# GPS.net
KiCad netlist of a schematic drawn in Altium Designer
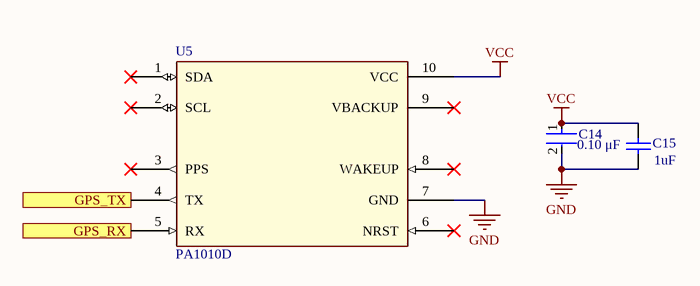
[diagram p0: GPS.SchDoc]

(export (version "E")
  (design (tool "Eeschema 10.0.6"))
  (components
    (comp (ref "C14")
      (value "C0603C104K5RACTU")
      (footprint "FP-C0603C-CF-MFG")
      (description "CAP CER 0.1UF 50V X7R 0603")
      (fields
        (field (name "TOLERANCE") "0.1")
        (field (name "MANUFACTURER") "KEMET")
        (field (name "CAPACITANCE") "0.10 μF")
      )
      (libsource (lib "Altium Content Vault") (part "b4654b650e69147ec39a6b967a45e02"))
    )
    (comp (ref "C15")
      (value "GRM21BR71H105KA12L")
      (footprint "CAPC2013X135X45LL10T25")
      (fields (field (name "MANUFACTURER") "Murata") (field (name "CAPACITANCE") "1uF"))
      (libsource (lib "Altium Content Vault") (part "CAP"))
    )
    (comp (ref "U5")
      (value "PA1010D")
      (footprint "PA1010D:PA1010D")
      (description "Ultraminiature GPS Module 10x10x6.8mm")
      (libsource (lib "PA1010D") (part "PA1010D"))
    )
  )
  (nets
    (net (code "1") (name "/GPS_RX") (class "Default")
      (node (ref "U5") (pin "5") (pinfunction "RX_5") (pintype "input"))
    )
    (net (code "2") (name "/GPS_TX") (class "Default")
      (node (ref "U5") (pin "4") (pinfunction "TX_4") (pintype "output"))
    )
    (net (code "3") (name "GND") (class "Default")
      (node (ref "C14") (pin "2") (pinfunction "2_2") (pintype "passive"))
      (node (ref "C15") (pin "1") (pinfunction "1_1") (pintype "passive"))
      (node (ref "U5") (pin "7") (pinfunction "GND_7") (pintype "passive"))
    )
    (net (code "4") (name "VCC") (class "Default")
      (node (ref "C14") (pin "1") (pinfunction "1_1") (pintype "passive"))
      (node (ref "C15") (pin "2") (pinfunction "2_2") (pintype "passive"))
      (node (ref "U5") (pin "10") (pinfunction "VCC_10") (pintype "passive"))
    )
    (net (code "5") (name "unconnected-(U5-NRST-Pad6)") (class "Default")
      (node (ref "U5") (pin "6") (pinfunction "NRST_6") (pintype "input+no_connect"))
    )
    (net (code "6") (name "unconnected-(U5-PPS-Pad3)") (class "Default")
      (node (ref "U5") (pin "3") (pinfunction "PPS_3") (pintype "output+no_connect"))
    )
    (net (code "7") (name "unconnected-(U5-SCL-Pad2)") (class "Default")
      (node (ref "U5") (pin "2") (pinfunction "SCL_2") (pintype "bidirectional+no_connect"))
    )
    (net (code "8") (name "unconnected-(U5-SDA-Pad1)") (class "Default")
      (node (ref "U5") (pin "1") (pinfunction "SDA_1") (pintype "bidirectional+no_connect"))
    )
    (net (code "9") (name "unconnected-(U5-VBACKUP-Pad9)") (class "Default")
      (node (ref "U5") (pin "9") (pinfunction "VBACKUP_9") (pintype "passive+no_connect"))
    )
    (net (code "10") (name "unconnected-(U5-WAKEUP-Pad8)") (class "Default")
      (node (ref "U5") (pin "8") (pinfunction "WAKEUP_8") (pintype "input+no_connect"))
    )
  )
)
